# stm32f103c8t6_basic.net
KiCad netlist of a schematic drawn in Altium Designer
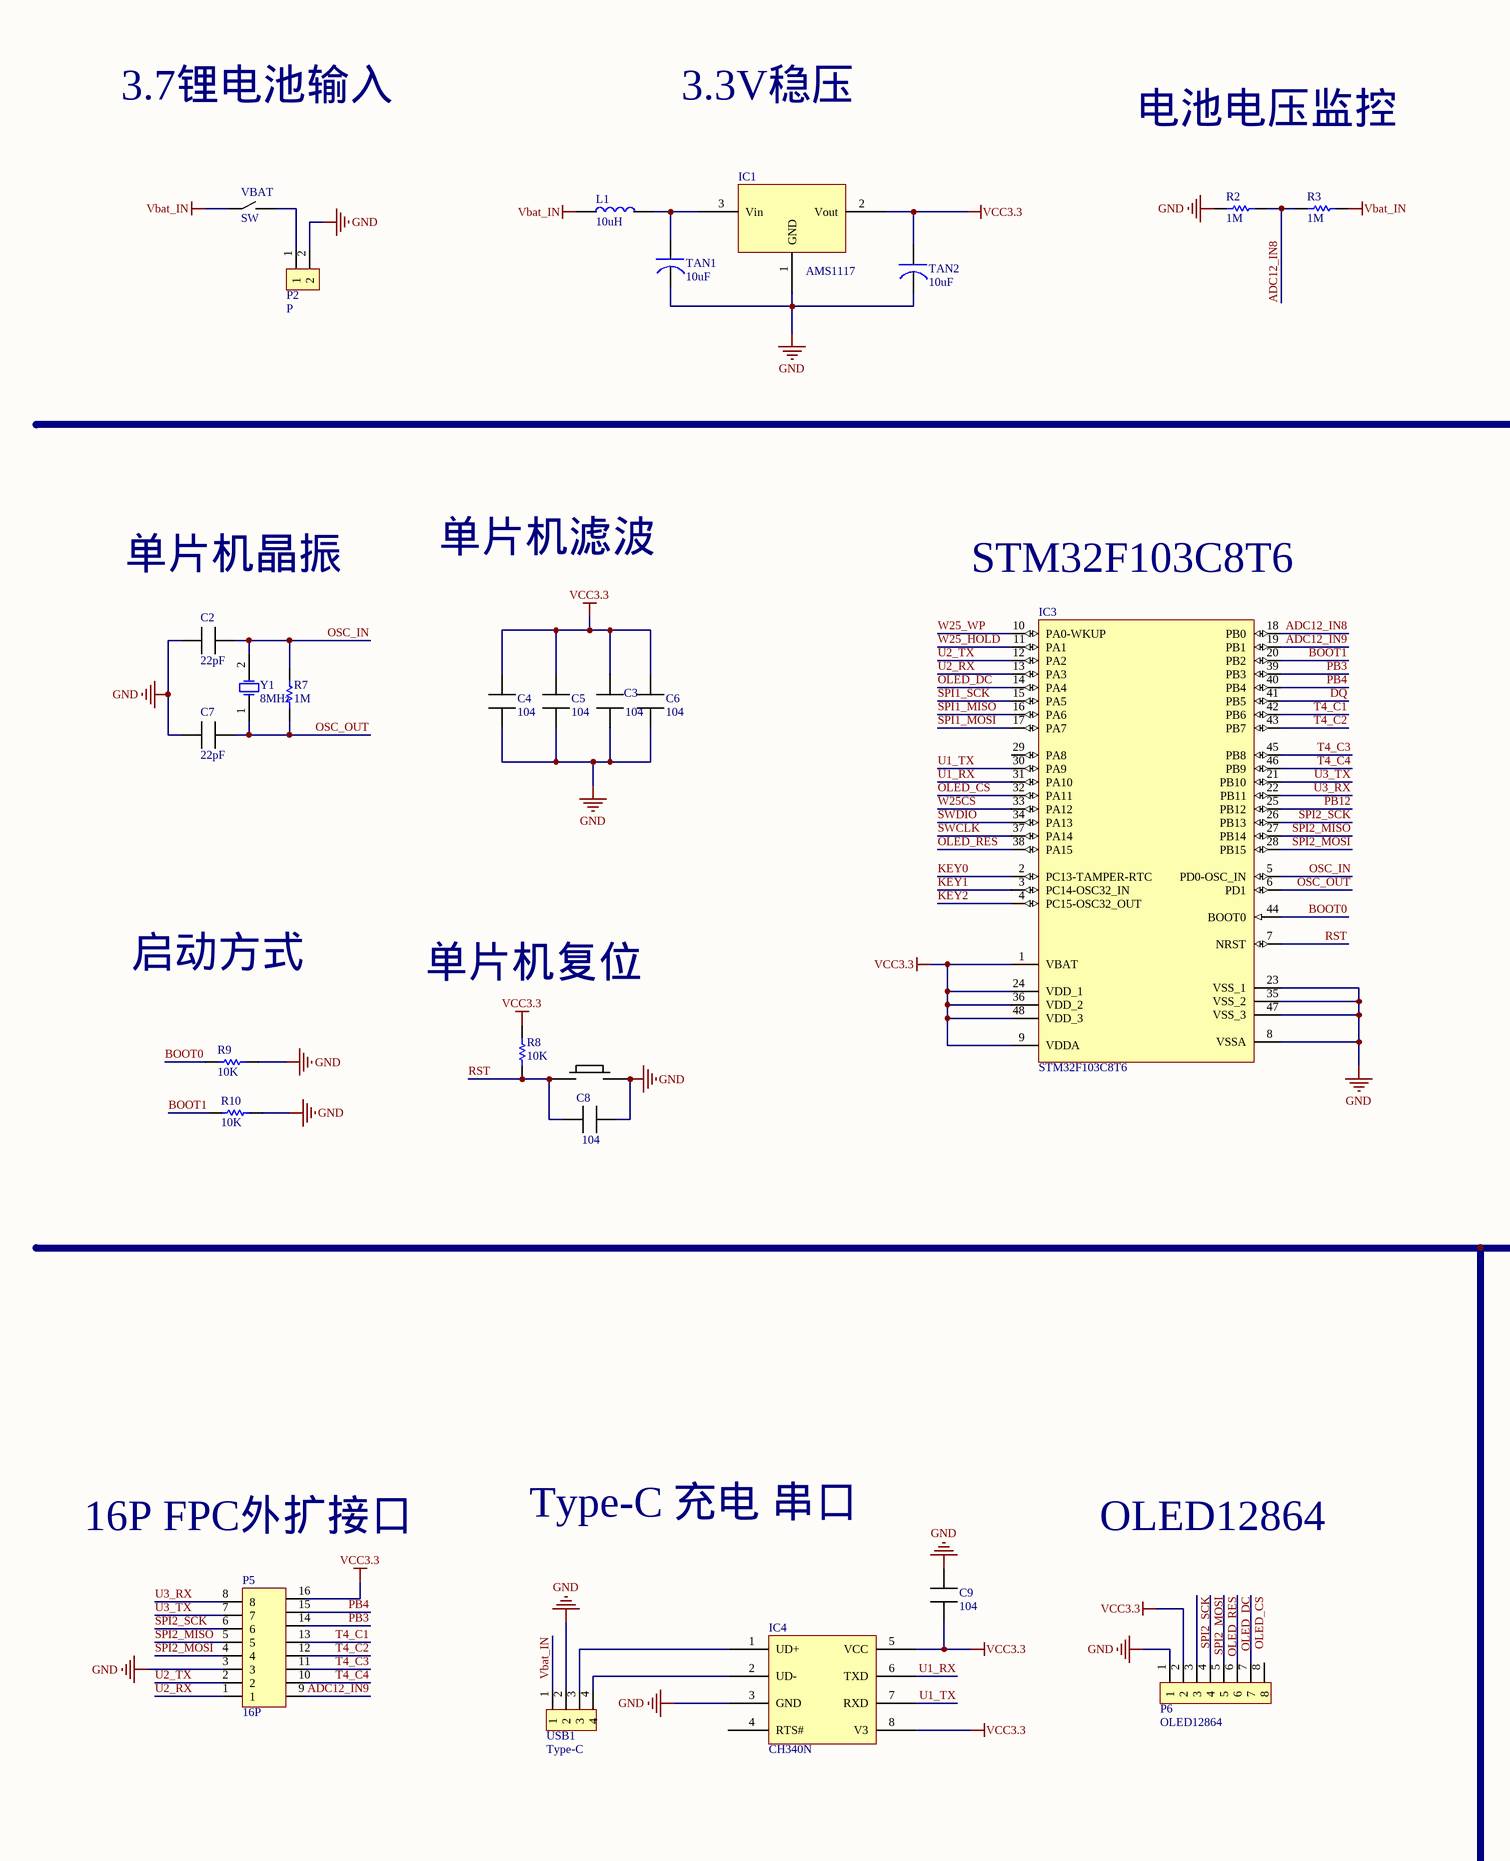
[diagram p0: stm32f103c8t6_basic.SchDoc, left]
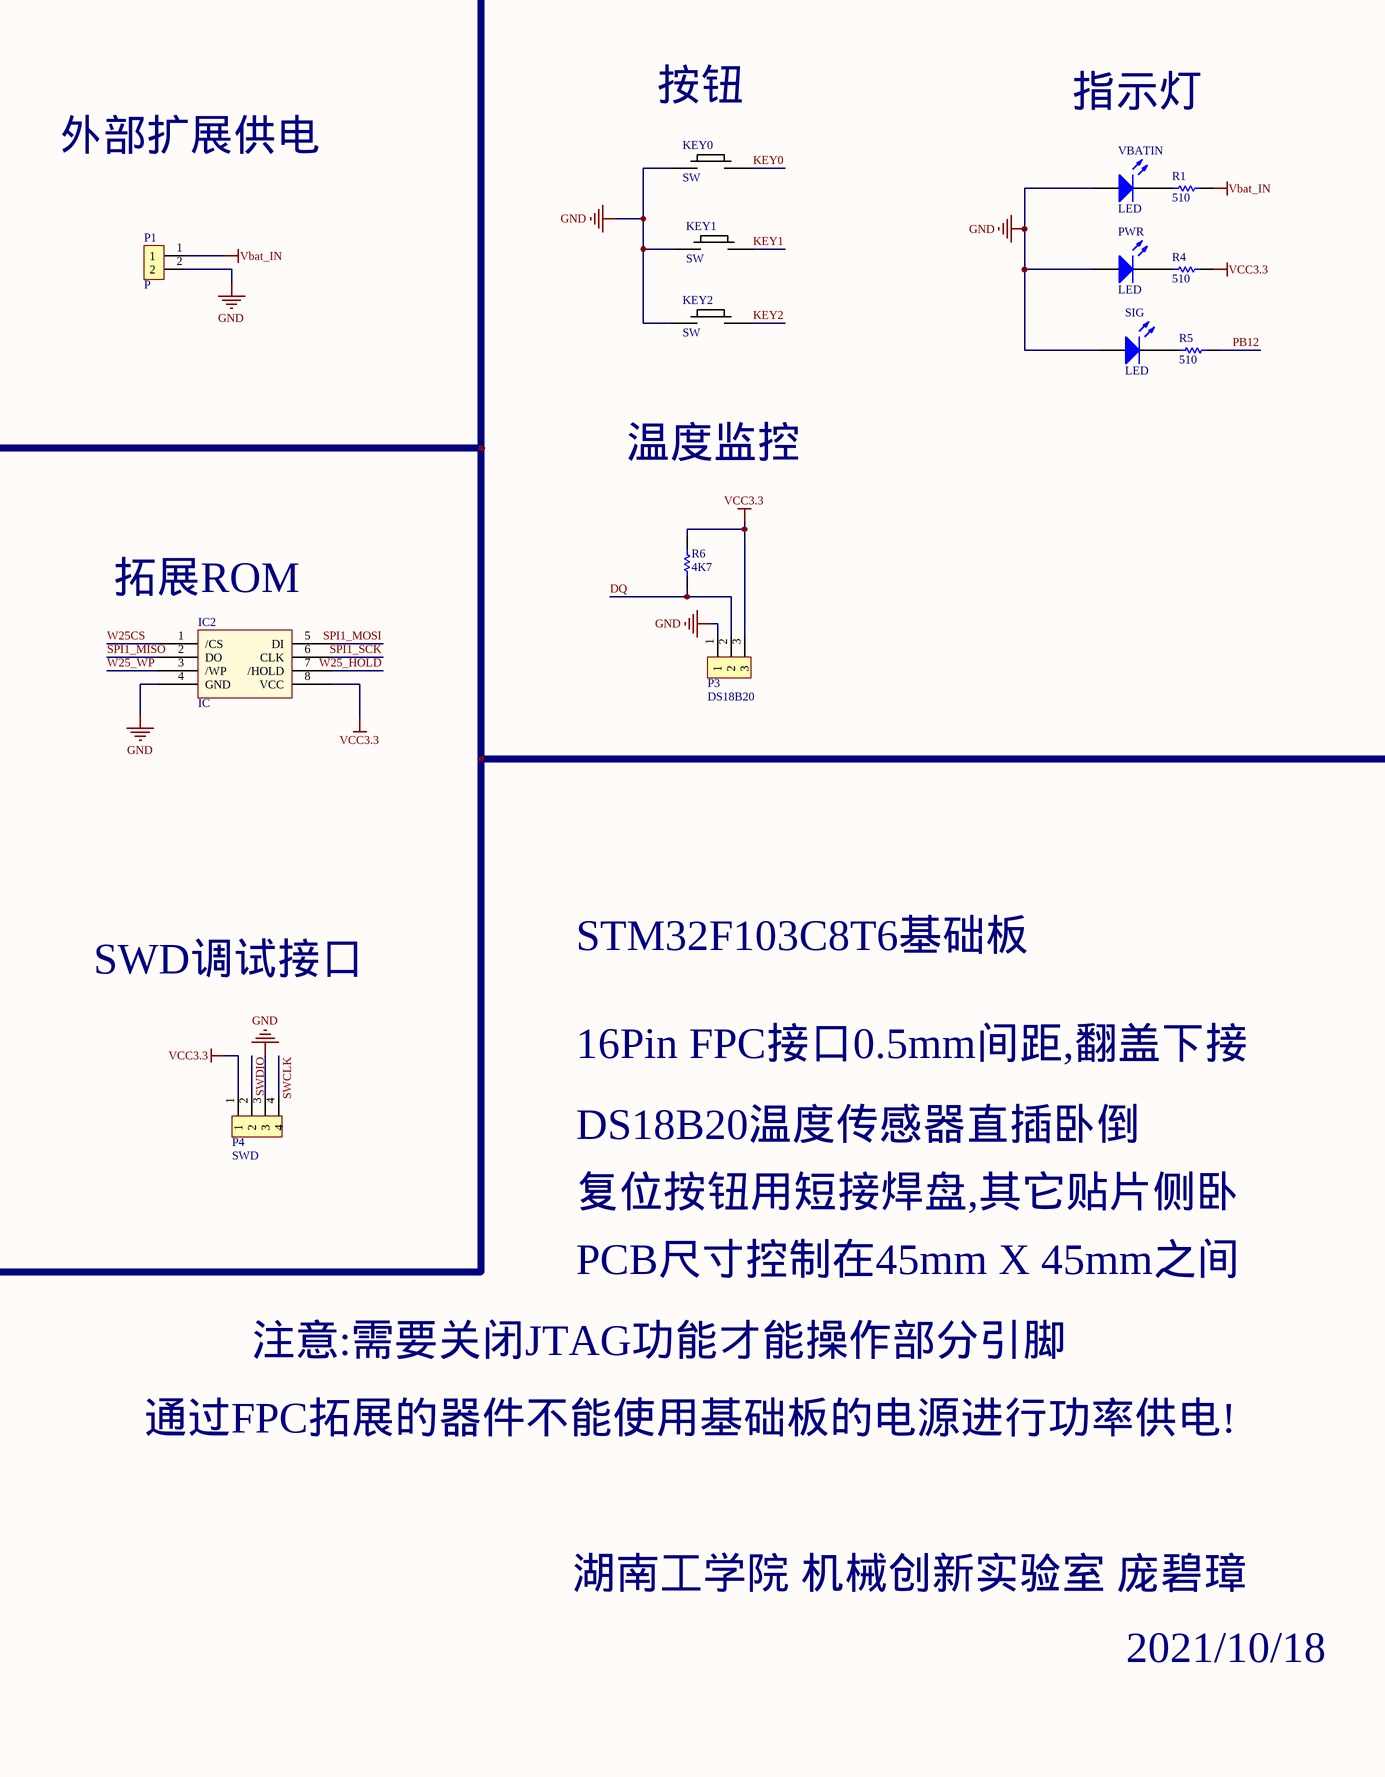
[diagram p1: stm32f103c8t6_basic.SchDoc, right]

(export (version "E")
  (design (tool "Eeschema 10.0.6"))
  (components
    (comp (ref "C2") (value "22pF") (footprint "C 0603") (libsource (lib "OledClock") (part "电容")))
    (comp (ref "C3") (value "104") (footprint "C 0603") (libsource (lib "OledClock") (part "电容")))
    (comp (ref "C4") (value "104") (footprint "C 0603") (libsource (lib "OledClock") (part "电容")))
    (comp (ref "C5") (value "104") (footprint "C 0603") (libsource (lib "OledClock") (part "电容")))
    (comp (ref "C6") (value "104") (footprint "C 0603") (libsource (lib "OledClock") (part "电容")))
    (comp (ref "C7") (value "22pF") (footprint "C 0603") (libsource (lib "OledClock") (part "电容")))
    (comp (ref "C8") (value "104") (footprint "C 0603") (libsource (lib "OledClock") (part "电容")))
    (comp (ref "C9") (value "104") (footprint "C 0603") (libsource (lib "OledClock") (part "电容")))
    (comp (ref "IC1")
      (value "AMS1117")
      (footprint "SOT-223")
      (libsource (lib "OledClock") (part "AMS1117-3.3"))
    )
    (comp (ref "IC2") (value "IC") (footprint "SOP-8") (libsource (lib "OledClock") (part "w25q16")))
    (comp (ref "IC3")
      (value "STM32F103C8T6")
      (footprint "LQPF48 7X7")
      (libsource (lib "OledClock") (part "stm32f103c8t6"))
    )
    (comp (ref "IC4")
      (value "CH340N")
      (footprint "SOP-8")
      (libsource (lib "altium-import") (part "root_0_CH340N_"))
    )
    (comp (ref "KEY0") (value "SW") (footprint "SW SMD 3x6x2.5") (libsource (lib "OledClock") (part "弹簧开关")))
    (comp (ref "KEY1") (value "SW") (footprint "SW SMD 3x6x2.5") (libsource (lib "OledClock") (part "弹簧开关")))
    (comp (ref "KEY2") (value "SW") (footprint "SW SMD 3x6x2.5") (libsource (lib "OledClock") (part "弹簧开关")))
    (comp (ref "L1") (value "10uH") (footprint "L 0603") (libsource (lib "OledClock") (part "电感")))
    (comp (ref "P1") (value "P") (footprint "HEAD_1X2") (libsource (lib "OledClock") (part "1X2排针")))
    (comp (ref "P2") (value "P") (footprint "电池焊盘") (libsource (lib "") (part "1X2排针_1")))
    (comp (ref "P3") (value "DS18B20") (footprint "TO92") (libsource (lib "OledClock") (part "1X3排针")))
    (comp (ref "P4") (value "SWD") (footprint "MX1.25") (libsource (lib "OledClock") (part "1X4排针")))
    (comp (ref "P5") (value "16P") (footprint "FPC 0.5mm 16P") (libsource (lib "OledClock") (part "16P")))
    (comp (ref "P6") (value "OLED12864") (footprint "HEAD_1X8") (libsource (lib "OledClock") (part "1X8排针")))
    (comp (ref "PWR")
      (value "LED")
      (footprint "LED 0603")
      (description "Typical INFRARED GaAs LED")
      (fields (field (name "PUBLISHER") "Altium Limited"))
      (libsource (lib "OledClock") (part "LED"))
    )
    (comp (ref "R1")
      (value "510")
      (footprint "R 0603")
      (description "Resistor")
      (fields (field (name "PUBLISHER") "Altium Limited"))
      (libsource (lib "OledClock") (part "Res"))
    )
    (comp (ref "R2")
      (value "1M")
      (footprint "R 0603")
      (description "Resistor")
      (fields (field (name "PUBLISHER") "Altium Limited"))
      (libsource (lib "OledClock") (part "Res"))
    )
    (comp (ref "R3")
      (value "1M")
      (footprint "R 0603")
      (description "Resistor")
      (fields (field (name "PUBLISHER") "Altium Limited"))
      (libsource (lib "OledClock") (part "Res"))
    )
    (comp (ref "R4")
      (value "510")
      (footprint "R 0603")
      (description "Resistor")
      (fields (field (name "PUBLISHER") "Altium Limited"))
      (libsource (lib "OledClock") (part "Res"))
    )
    (comp (ref "R5")
      (value "510")
      (footprint "R 0603")
      (description "Resistor")
      (fields (field (name "PUBLISHER") "Altium Limited"))
      (libsource (lib "OledClock") (part "Res"))
    )
    (comp (ref "R6")
      (value "4K7")
      (footprint "R 0603")
      (description "Resistor")
      (fields (field (name "PUBLISHER") "Altium Limited"))
      (libsource (lib "OledClock") (part "Res"))
    )
    (comp (ref "R7")
      (value "1M")
      (footprint "R 0603")
      (description "Resistor")
      (fields (field (name "PUBLISHER") "Altium Limited"))
      (libsource (lib "OledClock") (part "Res"))
    )
    (comp (ref "R8")
      (value "10K")
      (footprint "R 0603")
      (description "Resistor")
      (fields (field (name "PUBLISHER") "Altium Limited"))
      (libsource (lib "OledClock") (part "Res"))
    )
    (comp (ref "R9")
      (value "10K")
      (footprint "R 0603")
      (description "Resistor")
      (fields (field (name "PUBLISHER") "Altium Limited"))
      (libsource (lib "OledClock") (part "Res"))
    )
    (comp (ref "R10")
      (value "10K")
      (footprint "R 0603")
      (description "Resistor")
      (fields (field (name "PUBLISHER") "Altium Limited"))
      (libsource (lib "OledClock") (part "Res"))
    )
    (comp (ref "RST") (value "SW") (footprint "SW SMD 3x6x2.5") (libsource (lib "OledClock") (part "弹簧开关")))
    (comp (ref "SIG")
      (value "LED")
      (footprint "LED 0603")
      (description "Typical INFRARED GaAs LED")
      (fields (field (name "PUBLISHER") "Altium Limited"))
      (libsource (lib "OledClock") (part "LED"))
    )
    (comp (ref "TAN1") (value "10uF") (footprint "TAN 0805") (libsource (lib "OledClock") (part "极性电容")))
    (comp (ref "TAN2") (value "10uF") (footprint "TAN 0805") (libsource (lib "OledClock") (part "极性电容")))
    (comp (ref "USB1") (value "Type-C") (footprint "USB Type-C") (libsource (lib "OledClock") (part "1X4排针")))
    (comp (ref "VBAT") (value "SW") (footprint "拨动开关 9X3.5X3.5 侧卧") (libsource (lib "OledClock") (part "开关")))
    (comp (ref "VBATIN")
      (value "LED")
      (footprint "LED 0603")
      (description "Typical INFRARED GaAs LED")
      (fields (field (name "PUBLISHER") "Altium Limited"))
      (libsource (lib "OledClock") (part "LED"))
    )
    (comp (ref "Y1")
      (value "8MHz")
      (footprint "OSC SMD")
      (description "Crystal Oscillator")
      (fields (field (name "PUBLISHER") "Altium Limited"))
      (libsource (lib "OledClock") (part "晶振"))
    )
  )
  (nets
    (net (code "1") (name "/ADC12_IN8") (class "Default")
      (node (ref "IC3") (pin "18") (pinfunction "PB0_18") (pintype "bidirectional"))
      (node (ref "R2") (pin "1") (pinfunction "1_1") (pintype "passive"))
      (node (ref "R3") (pin "2") (pinfunction "2_2") (pintype "passive"))
    )
    (net (code "2") (name "/ADC12_IN9") (class "Default")
      (node (ref "IC3") (pin "19") (pinfunction "PB1_19") (pintype "bidirectional"))
      (node (ref "P5") (pin "9") (pinfunction "9_9") (pintype "passive"))
    )
    (net (code "3") (name "/BOOT0") (class "Default")
      (node (ref "IC3") (pin "44") (pinfunction "BOOT0_44") (pintype "input"))
      (node (ref "R9") (pin "2") (pinfunction "2_2") (pintype "passive"))
    )
    (net (code "4") (name "/BOOT1") (class "Default")
      (node (ref "IC3") (pin "20") (pinfunction "PB2_20") (pintype "bidirectional"))
      (node (ref "R10") (pin "2") (pinfunction "2_2") (pintype "passive"))
    )
    (net (code "5") (name "/DQ") (class "Default")
      (node (ref "IC3") (pin "41") (pinfunction "PB5_41") (pintype "bidirectional"))
      (node (ref "P3") (pin "2") (pinfunction "2_2") (pintype "passive"))
      (node (ref "R6") (pin "2") (pinfunction "2_2") (pintype "passive"))
    )
    (net (code "6") (name "/KEY0") (class "Default")
      (node (ref "IC3") (pin "2") (pinfunction "PC13-TAMPER-RTC_2") (pintype "bidirectional"))
      (node (ref "KEY0") (pin "2") (pinfunction "2_2") (pintype "passive"))
    )
    (net (code "7") (name "/KEY1") (class "Default")
      (node (ref "IC3") (pin "3") (pinfunction "PC14-OSC32_IN_3") (pintype "bidirectional"))
      (node (ref "KEY1") (pin "2") (pinfunction "2_2") (pintype "passive"))
    )
    (net (code "8") (name "/KEY2") (class "Default")
      (node (ref "IC3") (pin "4") (pinfunction "PC15-OSC32_OUT_4") (pintype "bidirectional"))
      (node (ref "KEY2") (pin "2") (pinfunction "2_2") (pintype "passive"))
    )
    (net (code "9") (name "/OLED_CS") (class "Default")
      (node (ref "IC3") (pin "32") (pinfunction "PA11_32") (pintype "bidirectional"))
      (node (ref "P6") (pin "7") (pinfunction "7_7") (pintype "passive"))
    )
    (net (code "10") (name "/OLED_DC") (class "Default")
      (node (ref "IC3") (pin "14") (pinfunction "PA4_14") (pintype "bidirectional"))
      (node (ref "P6") (pin "6") (pinfunction "6_6") (pintype "passive"))
    )
    (net (code "11") (name "/OLED_RES") (class "Default")
      (node (ref "IC3") (pin "38") (pinfunction "PA15_38") (pintype "bidirectional"))
      (node (ref "P6") (pin "5") (pinfunction "5_5") (pintype "passive"))
    )
    (net (code "12") (name "/OSC_IN") (class "Default")
      (node (ref "C2") (pin "2") (pinfunction "2_2") (pintype "passive"))
      (node (ref "IC3") (pin "5") (pinfunction "PD0-OSC_IN_5") (pintype "bidirectional"))
      (node (ref "R7") (pin "2") (pinfunction "2_2") (pintype "passive"))
      (node (ref "Y1") (pin "2") (pinfunction "OSC2_2") (pintype "passive"))
    )
    (net (code "13") (name "/OSC_OUT") (class "Default")
      (node (ref "C7") (pin "2") (pinfunction "2_2") (pintype "passive"))
      (node (ref "IC3") (pin "6") (pinfunction "PD1_6") (pintype "bidirectional"))
      (node (ref "R7") (pin "1") (pinfunction "1_1") (pintype "passive"))
      (node (ref "Y1") (pin "1") (pinfunction "OSC1_1") (pintype "passive"))
    )
    (net (code "14") (name "/PB3") (class "Default")
      (node (ref "IC3") (pin "39") (pinfunction "PB3_39") (pintype "bidirectional"))
      (node (ref "P5") (pin "14") (pinfunction "14_14") (pintype "passive"))
    )
    (net (code "15") (name "/PB4") (class "Default")
      (node (ref "IC3") (pin "40") (pinfunction "PB4_40") (pintype "bidirectional"))
      (node (ref "P5") (pin "15") (pinfunction "15_15") (pintype "passive"))
    )
    (net (code "16") (name "/PB12") (class "Default")
      (node (ref "IC3") (pin "25") (pinfunction "PB12_25") (pintype "bidirectional"))
      (node (ref "R5") (pin "1") (pinfunction "1_1") (pintype "passive"))
    )
    (net (code "17") (name "/RST") (class "Default")
      (node (ref "C8") (pin "1") (pinfunction "1_1") (pintype "passive"))
      (node (ref "IC3") (pin "7") (pinfunction "NRST_7") (pintype "bidirectional"))
      (node (ref "R8") (pin "1") (pinfunction "1_1") (pintype "passive"))
      (node (ref "RST") (pin "1") (pinfunction "1_1") (pintype "passive"))
    )
    (net (code "18") (name "/SPI1_MISO") (class "Default")
      (node (ref "IC2") (pin "2") (pinfunction "DO_2") (pintype "passive"))
      (node (ref "IC3") (pin "16") (pinfunction "PA6_16") (pintype "bidirectional"))
    )
    (net (code "19") (name "/SPI1_MOSI") (class "Default")
      (node (ref "IC2") (pin "5") (pinfunction "DI_5") (pintype "passive"))
      (node (ref "IC3") (pin "17") (pinfunction "PA7_17") (pintype "bidirectional"))
    )
    (net (code "20") (name "/SPI1_SCK") (class "Default")
      (node (ref "IC2") (pin "6") (pinfunction "CLK_6") (pintype "passive"))
      (node (ref "IC3") (pin "15") (pinfunction "PA5_15") (pintype "bidirectional"))
    )
    (net (code "21") (name "/SPI2_MISO") (class "Default")
      (node (ref "IC3") (pin "27") (pinfunction "PB14_27") (pintype "bidirectional"))
      (node (ref "P5") (pin "5") (pinfunction "5_5") (pintype "passive"))
    )
    (net (code "22") (name "/SPI2_MOSI") (class "Default")
      (node (ref "IC3") (pin "28") (pinfunction "PB15_28") (pintype "bidirectional"))
      (node (ref "P5") (pin "4") (pinfunction "4_4") (pintype "passive"))
      (node (ref "P6") (pin "4") (pinfunction "4_4") (pintype "passive"))
    )
    (net (code "23") (name "/SPI2_SCK") (class "Default")
      (node (ref "IC3") (pin "26") (pinfunction "PB13_26") (pintype "bidirectional"))
      (node (ref "P5") (pin "6") (pinfunction "6_6") (pintype "passive"))
      (node (ref "P6") (pin "3") (pinfunction "3_3") (pintype "passive"))
    )
    (net (code "24") (name "/SWCLK") (class "Default")
      (node (ref "IC3") (pin "37") (pinfunction "PA14_37") (pintype "bidirectional"))
      (node (ref "P4") (pin "4") (pinfunction "4_4") (pintype "passive"))
    )
    (net (code "25") (name "/SWDIO") (class "Default")
      (node (ref "IC3") (pin "34") (pinfunction "PA13_34") (pintype "bidirectional"))
      (node (ref "P4") (pin "2") (pinfunction "2_2") (pintype "passive"))
    )
    (net (code "26") (name "/T4_C1") (class "Default")
      (node (ref "IC3") (pin "42") (pinfunction "PB6_42") (pintype "bidirectional"))
      (node (ref "P5") (pin "13") (pinfunction "13_13") (pintype "passive"))
    )
    (net (code "27") (name "/T4_C2") (class "Default")
      (node (ref "IC3") (pin "43") (pinfunction "PB7_43") (pintype "bidirectional"))
      (node (ref "P5") (pin "12") (pinfunction "12_12") (pintype "passive"))
    )
    (net (code "28") (name "/T4_C3") (class "Default")
      (node (ref "IC3") (pin "45") (pinfunction "PB8_45") (pintype "bidirectional"))
      (node (ref "P5") (pin "11") (pinfunction "11_11") (pintype "passive"))
    )
    (net (code "29") (name "/T4_C4") (class "Default")
      (node (ref "IC3") (pin "46") (pinfunction "PB9_46") (pintype "bidirectional"))
      (node (ref "P5") (pin "10") (pinfunction "10_10") (pintype "passive"))
    )
    (net (code "30") (name "/U1_RX") (class "Default")
      (node (ref "IC3") (pin "31") (pinfunction "PA10_31") (pintype "bidirectional"))
      (node (ref "IC4") (pin "6") (pinfunction "TXD_6") (pintype "passive"))
    )
    (net (code "31") (name "/U1_TX") (class "Default")
      (node (ref "IC3") (pin "30") (pinfunction "PA9_30") (pintype "bidirectional"))
      (node (ref "IC4") (pin "7") (pinfunction "RXD_7") (pintype "passive"))
    )
    (net (code "32") (name "/U2_RX") (class "Default")
      (node (ref "IC3") (pin "13") (pinfunction "PA3_13") (pintype "bidirectional"))
      (node (ref "P5") (pin "1") (pinfunction "1_1") (pintype "passive"))
    )
    (net (code "33") (name "/U2_TX") (class "Default")
      (node (ref "IC3") (pin "12") (pinfunction "PA2_12") (pintype "bidirectional"))
      (node (ref "P5") (pin "2") (pinfunction "2_2") (pintype "passive"))
    )
    (net (code "34") (name "/U3_RX") (class "Default")
      (node (ref "IC3") (pin "22") (pinfunction "PB11_22") (pintype "bidirectional"))
      (node (ref "P5") (pin "8") (pinfunction "8_8") (pintype "passive"))
    )
    (net (code "35") (name "/U3_TX") (class "Default")
      (node (ref "IC3") (pin "21") (pinfunction "PB10_21") (pintype "bidirectional"))
      (node (ref "P5") (pin "7") (pinfunction "7_7") (pintype "passive"))
    )
    (net (code "36") (name "/W25CS") (class "Default")
      (node (ref "IC2") (pin "1") (pinfunction "/CS_1") (pintype "passive"))
      (node (ref "IC3") (pin "33") (pinfunction "PA12_33") (pintype "bidirectional"))
    )
    (net (code "37") (name "/W25_HOLD") (class "Default")
      (node (ref "IC2") (pin "7") (pinfunction "/HOLD_7") (pintype "passive"))
      (node (ref "IC3") (pin "11") (pinfunction "PA1_11") (pintype "bidirectional"))
    )
    (net (code "38") (name "/W25_WP") (class "Default")
      (node (ref "IC2") (pin "3") (pinfunction "/WP_3") (pintype "passive"))
      (node (ref "IC3") (pin "10") (pinfunction "PA0-WKUP_10") (pintype "bidirectional"))
    )
    (net (code "39") (name "GND") (class "Default")
      (node (ref "C2") (pin "1") (pinfunction "1_1") (pintype "passive"))
      (node (ref "C3") (pin "1") (pinfunction "1_1") (pintype "passive"))
      (node (ref "C4") (pin "1") (pinfunction "1_1") (pintype "passive"))
      (node (ref "C5") (pin "1") (pinfunction "1_1") (pintype "passive"))
      (node (ref "C6") (pin "1") (pinfunction "1_1") (pintype "passive"))
      (node (ref "C7") (pin "1") (pinfunction "1_1") (pintype "passive"))
      (node (ref "C8") (pin "2") (pinfunction "2_2") (pintype "passive"))
      (node (ref "C9") (pin "2") (pinfunction "2_2") (pintype "passive"))
      (node (ref "IC1") (pin "1") (pinfunction "GND_1") (pintype "passive"))
      (node (ref "IC2") (pin "4") (pinfunction "GND_4") (pintype "passive"))
      (node (ref "IC3") (pin "23") (pinfunction "VSS_1_23") (pintype "power_in"))
      (node (ref "IC3") (pin "35") (pinfunction "VSS_2_35") (pintype "power_in"))
      (node (ref "IC3") (pin "47") (pinfunction "VSS_3_47") (pintype "power_in"))
      (node (ref "IC3") (pin "8") (pinfunction "VSSA_8") (pintype "power_in"))
      (node (ref "IC4") (pin "3") (pinfunction "GND_3") (pintype "passive"))
      (node (ref "KEY0") (pin "1") (pinfunction "1_1") (pintype "passive"))
      (node (ref "KEY1") (pin "1") (pinfunction "1_1") (pintype "passive"))
      (node (ref "KEY2") (pin "1") (pinfunction "1_1") (pintype "passive"))
      (node (ref "P1") (pin "2") (pinfunction "2_2") (pintype "passive"))
      (node (ref "P2") (pin "2") (pinfunction "2_2") (pintype "passive"))
      (node (ref "P3") (pin "1") (pinfunction "1_1") (pintype "passive"))
      (node (ref "P4") (pin "3") (pinfunction "3_3") (pintype "passive"))
      (node (ref "P5") (pin "3") (pinfunction "3_3") (pintype "passive"))
      (node (ref "P6") (pin "1") (pinfunction "1_1") (pintype "passive"))
      (node (ref "PWR") (pin "1") (pinfunction "A_1") (pintype "passive"))
      (node (ref "R10") (pin "1") (pinfunction "1_1") (pintype "passive"))
      (node (ref "R2") (pin "2") (pinfunction "2_2") (pintype "passive"))
      (node (ref "R9") (pin "1") (pinfunction "1_1") (pintype "passive"))
      (node (ref "RST") (pin "2") (pinfunction "2_2") (pintype "passive"))
      (node (ref "SIG") (pin "1") (pinfunction "A_1") (pintype "passive"))
      (node (ref "TAN1") (pin "1") (pinfunction "1_1") (pintype "passive"))
      (node (ref "TAN2") (pin "1") (pinfunction "1_1") (pintype "passive"))
      (node (ref "USB1") (pin "2") (pinfunction "2_2") (pintype "passive"))
      (node (ref "VBATIN") (pin "1") (pinfunction "A_1") (pintype "passive"))
    )
    (net (code "40") (name "Net-(IC1-Vin)") (class "Default")
      (node (ref "IC1") (pin "3") (pinfunction "Vin_3") (pintype "passive"))
      (node (ref "L1") (pin "2") (pinfunction "2_2") (pintype "passive"))
      (node (ref "TAN1") (pin "2") (pinfunction "2_2") (pintype "passive"))
    )
    (net (code "41") (name "Net-(IC4-UD+)") (class "Default")
      (node (ref "IC4") (pin "1") (pinfunction "UD+_1") (pintype "passive"))
      (node (ref "USB1") (pin "3") (pinfunction "3_3") (pintype "passive"))
    )
    (net (code "42") (name "Net-(IC4-UD-)") (class "Default")
      (node (ref "IC4") (pin "2") (pinfunction "UD-_2") (pintype "passive"))
      (node (ref "USB1") (pin "4") (pinfunction "4_4") (pintype "passive"))
    )
    (net (code "43") (name "Net-(P2-Pad1)") (class "Default")
      (node (ref "P2") (pin "1") (pinfunction "1_1") (pintype "passive"))
      (node (ref "VBAT") (pin "1") (pinfunction "1_1") (pintype "passive"))
    )
    (net (code "44") (name "Net-(PWR-K)") (class "Default")
      (node (ref "PWR") (pin "2") (pinfunction "K_2") (pintype "passive"))
      (node (ref "R4") (pin "2") (pinfunction "2_2") (pintype "passive"))
    )
    (net (code "45") (name "Net-(SIG-K)") (class "Default")
      (node (ref "R5") (pin "2") (pinfunction "2_2") (pintype "passive"))
      (node (ref "SIG") (pin "2") (pinfunction "K_2") (pintype "passive"))
    )
    (net (code "46") (name "Net-(VBATIN-K)") (class "Default")
      (node (ref "R1") (pin "2") (pinfunction "2_2") (pintype "passive"))
      (node (ref "VBATIN") (pin "2") (pinfunction "K_2") (pintype "passive"))
    )
    (net (code "47") (name "VCC3.3") (class "Default")
      (node (ref "C3") (pin "2") (pinfunction "2_2") (pintype "passive"))
      (node (ref "C4") (pin "2") (pinfunction "2_2") (pintype "passive"))
      (node (ref "C5") (pin "2") (pinfunction "2_2") (pintype "passive"))
      (node (ref "C6") (pin "2") (pinfunction "2_2") (pintype "passive"))
      (node (ref "C9") (pin "1") (pinfunction "1_1") (pintype "passive"))
      (node (ref "IC1") (pin "2") (pinfunction "Vout_2") (pintype "passive"))
      (node (ref "IC2") (pin "8") (pinfunction "VCC_8") (pintype "passive"))
      (node (ref "IC3") (pin "1") (pinfunction "VBAT_1") (pintype "power_in"))
      (node (ref "IC3") (pin "24") (pinfunction "VDD_1_24") (pintype "power_in"))
      (node (ref "IC3") (pin "36") (pinfunction "VDD_2_36") (pintype "power_in"))
      (node (ref "IC3") (pin "48") (pinfunction "VDD_3_48") (pintype "power_in"))
      (node (ref "IC3") (pin "9") (pinfunction "VDDA_9") (pintype "power_in"))
      (node (ref "IC4") (pin "5") (pinfunction "VCC_5") (pintype "passive"))
      (node (ref "IC4") (pin "8") (pinfunction "V3_8") (pintype "passive"))
      (node (ref "P3") (pin "3") (pinfunction "3_3") (pintype "passive"))
      (node (ref "P4") (pin "1") (pinfunction "1_1") (pintype "passive"))
      (node (ref "P5") (pin "16") (pinfunction "16_16") (pintype "passive"))
      (node (ref "P6") (pin "2") (pinfunction "2_2") (pintype "passive"))
      (node (ref "R4") (pin "1") (pinfunction "1_1") (pintype "passive"))
      (node (ref "R6") (pin "1") (pinfunction "1_1") (pintype "passive"))
      (node (ref "R8") (pin "2") (pinfunction "2_2") (pintype "passive"))
      (node (ref "TAN2") (pin "2") (pinfunction "2_2") (pintype "passive"))
    )
    (net (code "48") (name "Vbat_IN") (class "Default")
      (node (ref "L1") (pin "1") (pinfunction "1_1") (pintype "passive"))
      (node (ref "P1") (pin "1") (pinfunction "1_1") (pintype "passive"))
      (node (ref "R1") (pin "1") (pinfunction "1_1") (pintype "passive"))
      (node (ref "R3") (pin "1") (pinfunction "1_1") (pintype "passive"))
      (node (ref "USB1") (pin "1") (pinfunction "1_1") (pintype "passive"))
      (node (ref "VBAT") (pin "2") (pinfunction "2_2") (pintype "passive"))
    )
    (net (code "49") (name "unconnected-(IC3-PA8-Pad29)") (class "Default")
      (node (ref "IC3") (pin "29") (pinfunction "PA8_29") (pintype "bidirectional"))
    )
    (net (code "50") (name "unconnected-(IC4-RTS#-Pad4)") (class "Default")
      (node (ref "IC4") (pin "4") (pinfunction "RTS#_4") (pintype "passive"))
    )
    (net (code "51") (name "unconnected-(P6-Pad8)") (class "Default")
      (node (ref "P6") (pin "8") (pinfunction "8_8") (pintype "passive"))
    )
  )
)
